# IMX291.net
KiCad netlist of a schematic drawn in Altium Designer
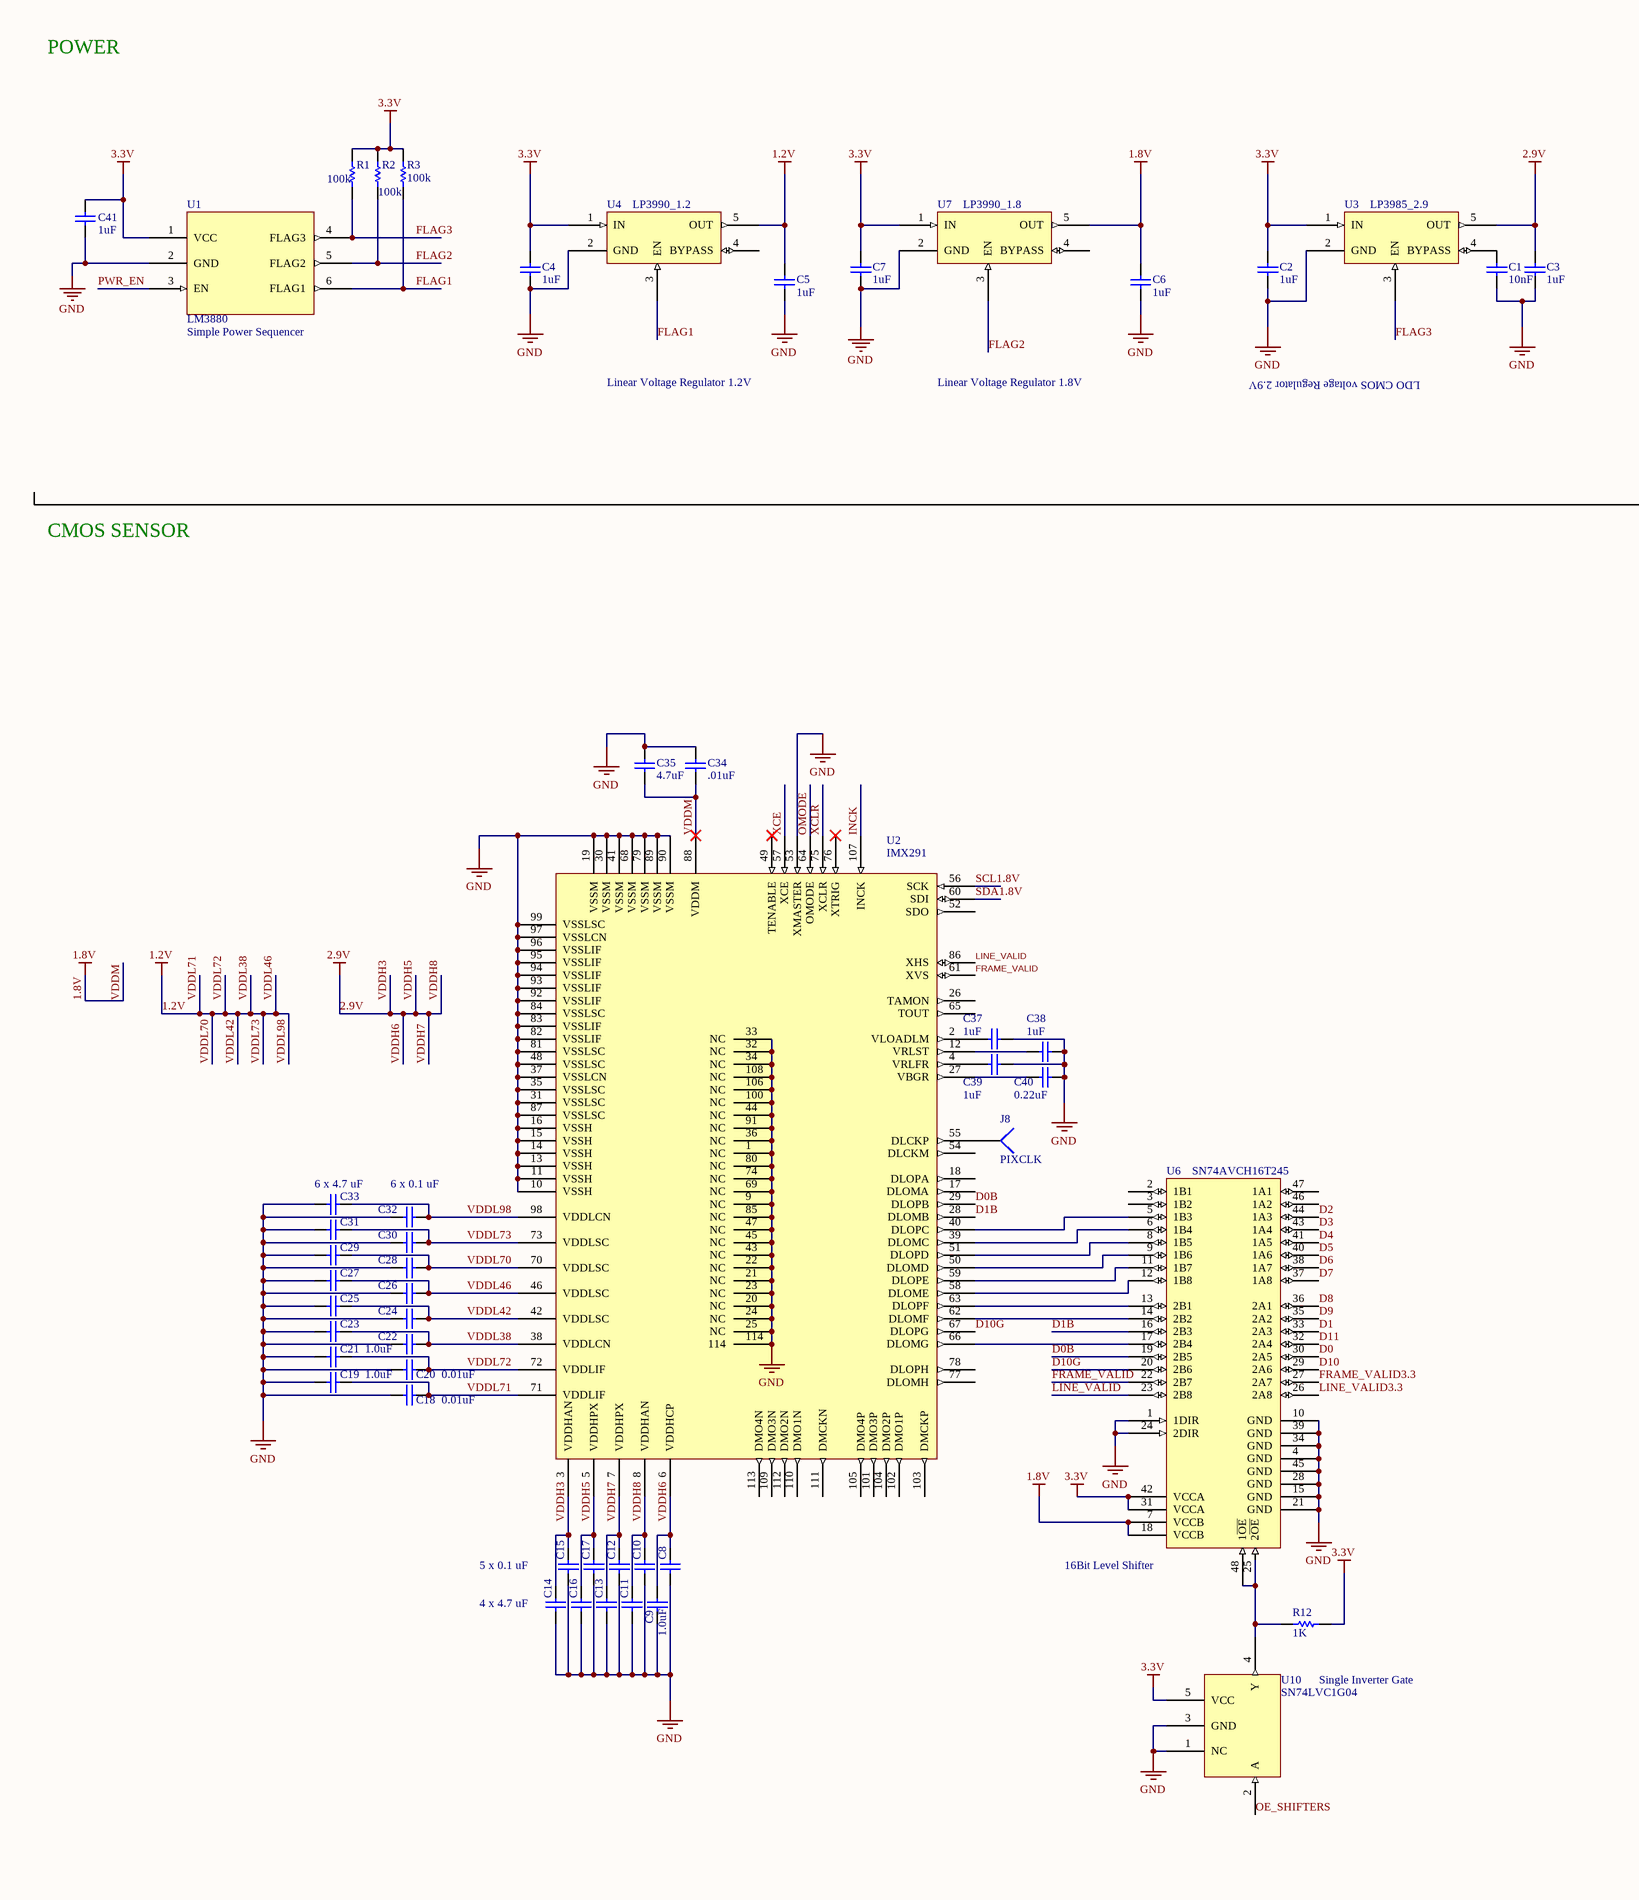
[diagram p0: IMX291.SchDoc, left]
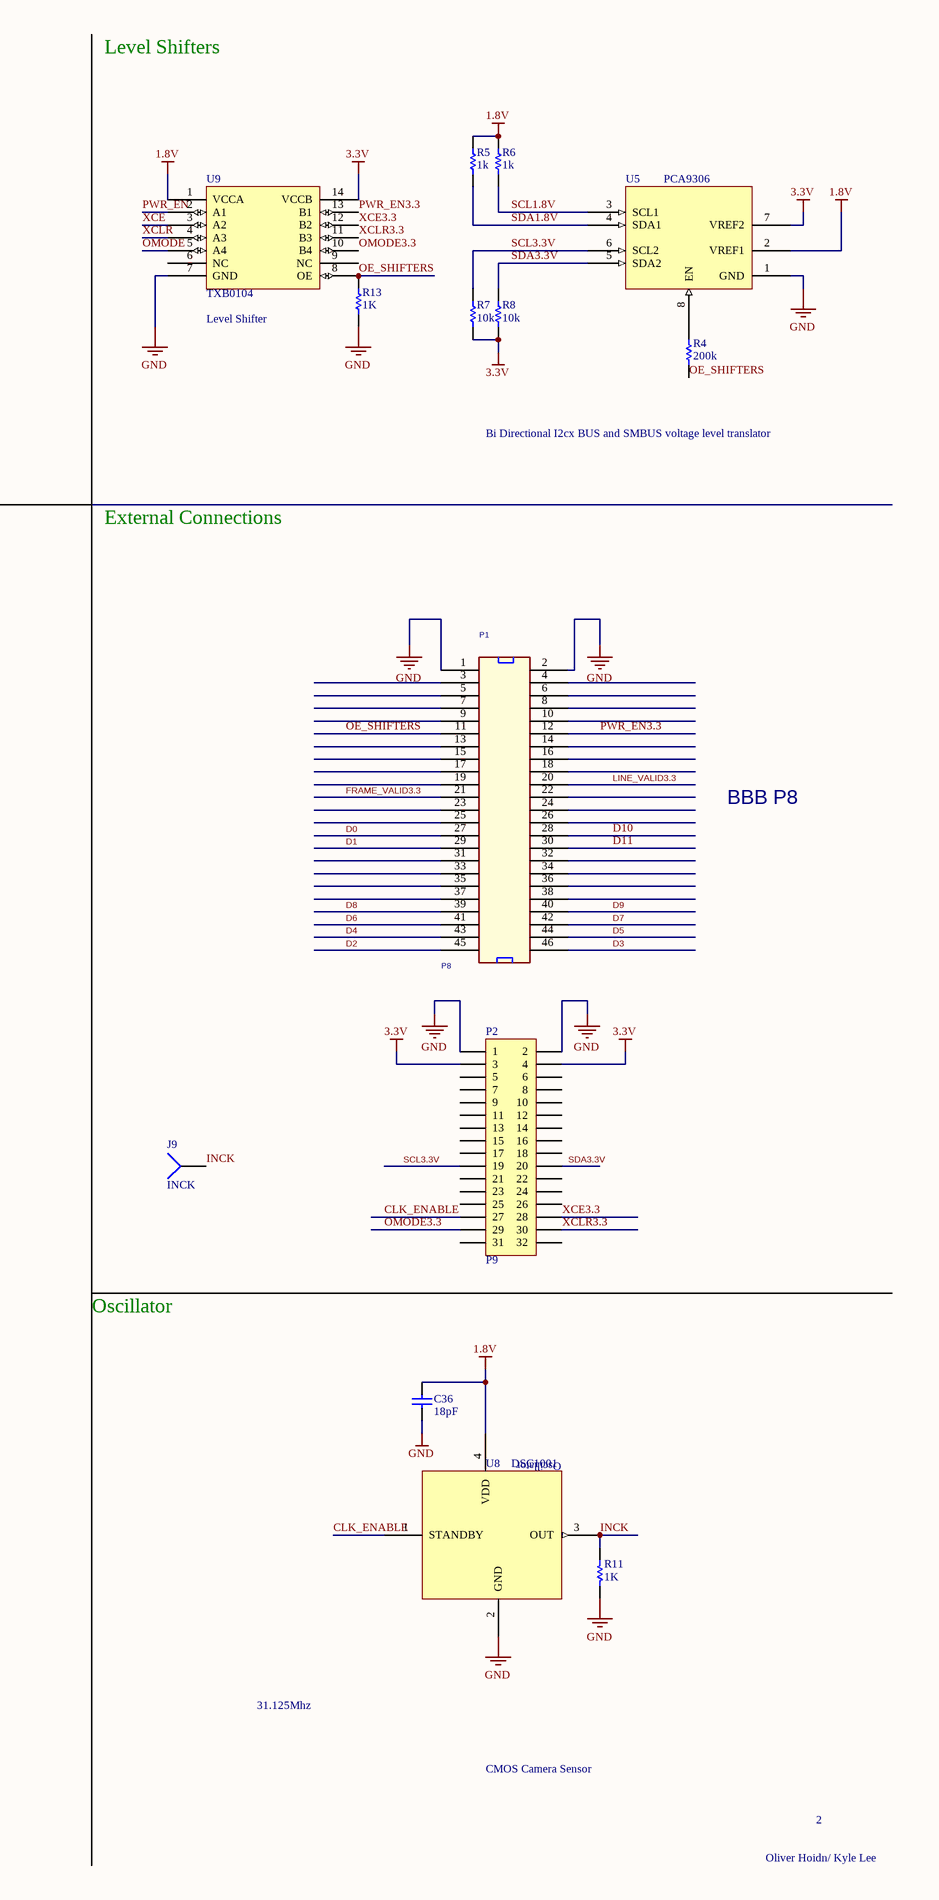
[diagram p1: IMX291.SchDoc, right]

(export (version "E")
  (design (tool "Eeschema 10.0.6"))
  (components
    (comp (ref "C1") (value "10nF") (footprint "0402") (libsource (lib "IMX291") (part "cap")))
    (comp (ref "C2") (value "1uF") (footprint "0402") (libsource (lib "IMX291") (part "cap")))
    (comp (ref "C3") (value "1uF") (footprint "0402") (libsource (lib "IMX291") (part "cap")))
    (comp (ref "C4") (value "1uF") (footprint "0402") (libsource (lib "IMX291") (part "cap")))
    (comp (ref "C5") (value "1uF") (footprint "0402") (libsource (lib "IMX291") (part "cap")))
    (comp (ref "C6") (value "1uF") (footprint "0402") (libsource (lib "IMX291") (part "cap")))
    (comp (ref "C7") (value "1uF") (footprint "0402") (libsource (lib "IMX291") (part "cap")))
    (comp (ref "C8") (value "0.1uF") (footprint "0402") (libsource (lib "IMX291") (part "cap")))
    (comp (ref "C9") (value "1.0uF") (footprint "0402") (libsource (lib "IMX291") (part "cap")))
    (comp (ref "C10") (value "0.1uF") (footprint "0402") (libsource (lib "IMX291") (part "cap")))
    (comp (ref "C11") (value "4.7uF") (footprint "0402") (libsource (lib "IMX291") (part "cap")))
    (comp (ref "C12") (value "0.1uF") (footprint "0402") (libsource (lib "IMX291") (part "cap")))
    (comp (ref "C13") (value "4.7uF") (footprint "0402") (libsource (lib "IMX291") (part "cap")))
    (comp (ref "C14") (value "4.7uF") (footprint "0402") (libsource (lib "IMX291") (part "cap")))
    (comp (ref "C15") (value "0.1uF") (footprint "0402") (libsource (lib "IMX291") (part "cap")))
    (comp (ref "C16") (value "4.7uF") (footprint "0402") (libsource (lib "IMX291") (part "cap")))
    (comp (ref "C17") (value "0.1uF") (footprint "0402") (libsource (lib "IMX291") (part "cap")))
    (comp (ref "C18") (value "0.01uF") (footprint "0402") (libsource (lib "IMX291") (part "cap")))
    (comp (ref "C19") (value "1.0uF") (footprint "0402") (libsource (lib "IMX291") (part "cap")))
    (comp (ref "C20") (value "0.01uF") (footprint "0402") (libsource (lib "IMX291") (part "cap")))
    (comp (ref "C21") (value "1.0uF") (footprint "0402") (libsource (lib "IMX291") (part "cap")))
    (comp (ref "C22") (value "0.1uF") (footprint "0402") (libsource (lib "IMX291") (part "cap")))
    (comp (ref "C23") (value "4.7uF") (footprint "0402") (libsource (lib "IMX291") (part "cap")))
    (comp (ref "C24") (value "0.1uF") (footprint "0402") (libsource (lib "IMX291") (part "cap")))
    (comp (ref "C25") (value "4.7uF") (footprint "0402") (libsource (lib "IMX291") (part "cap")))
    (comp (ref "C26") (value "0.1uF") (footprint "0402") (libsource (lib "IMX291") (part "cap")))
    (comp (ref "C27") (value "4.7uF") (footprint "0402") (libsource (lib "IMX291") (part "cap")))
    (comp (ref "C28") (value "0.1uF") (footprint "0402") (libsource (lib "IMX291") (part "cap")))
    (comp (ref "C29") (value "4.7uF") (footprint "0402") (libsource (lib "IMX291") (part "cap")))
    (comp (ref "C30") (value "0.1uF") (footprint "0402") (libsource (lib "IMX291") (part "cap")))
    (comp (ref "C31") (value "4.7uF") (footprint "0402") (libsource (lib "IMX291") (part "cap")))
    (comp (ref "C32") (value "0.1uF") (footprint "0402") (libsource (lib "IMX291") (part "cap")))
    (comp (ref "C33") (value "4.7uF") (footprint "0402") (libsource (lib "IMX291") (part "cap")))
    (comp (ref "C34") (value ".01uF") (footprint "0402") (libsource (lib "IMX291") (part "cap")))
    (comp (ref "C35") (value "4.7uF") (footprint "0402") (libsource (lib "IMX291") (part "cap")))
    (comp (ref "C36") (value "18pF") (footprint "0402") (libsource (lib "IMX291") (part "cap")))
    (comp (ref "C37") (value "1uF") (footprint "0402") (libsource (lib "IMX291") (part "cap")))
    (comp (ref "C38") (value "1uF") (footprint "0402") (libsource (lib "IMX291") (part "cap")))
    (comp (ref "C39") (value "1uF") (footprint "0402") (libsource (lib "IMX291") (part "cap")))
    (comp (ref "C40") (value "0.22uF") (footprint "0402") (libsource (lib "IMX291") (part "cap")))
    (comp (ref "C41") (value "1uF") (footprint "0402") (libsource (lib "IMX291") (part "cap")))
    (comp (ref "J8")
      (value "PIXCLK")
      (footprint "PIN1")
      (description "Socket")
      (fields (field (name "PUBLISHER") "Altium Limited"))
      (libsource (lib "IMX291") (part "Socket"))
    )
    (comp (ref "J9")
      (value "INCK")
      (footprint "PIN1")
      (description "Socket")
      (fields (field (name "PUBLISHER") "Altium Limited"))
      (libsource (lib "IMX291") (part "Socket"))
    )
    (comp (ref "P1")
      (value "P8")
      (description "CONN HEADER FMAL 46PS.1\" DL GOLD")
      (fields
        (field (name "MANUFACTURER") "Sullins Connector Solutions")
        (field (name "MANUFACTURER PART NUMBER") "PPPC232LFBN-RC")
      )
      (libsource (lib "IMX291") (part "HDR_46_F_2_0.1_0.1"))
    )
    (comp (ref "P2")
      (value "P9")
      (footprint "HDR2X16")
      (fields (field (name "PUBLISHER") "Altium Limited"))
      (libsource (lib "IMX291") (part "Header 16X2"))
    )
    (comp (ref "R1")
      (value "100k")
      (footprint "0402")
      (description "resistor")
      (libsource (lib "IMX291") (part "res"))
    )
    (comp (ref "R2")
      (value "100k")
      (footprint "0402")
      (description "resistor")
      (libsource (lib "IMX291") (part "res"))
    )
    (comp (ref "R3")
      (value "100k")
      (footprint "0402")
      (description "resistor")
      (libsource (lib "IMX291") (part "res"))
    )
    (comp (ref "R4")
      (value "200k")
      (footprint "0402")
      (description "resistor")
      (libsource (lib "IMX291") (part "res"))
    )
    (comp (ref "R5")
      (value "1k")
      (footprint "0402")
      (description "resistor")
      (libsource (lib "IMX291") (part "res"))
    )
    (comp (ref "R6")
      (value "1k")
      (footprint "0402")
      (description "resistor")
      (libsource (lib "IMX291") (part "res"))
    )
    (comp (ref "R7")
      (value "10k")
      (footprint "0603")
      (description "resistor")
      (libsource (lib "IMX291") (part "res"))
    )
    (comp (ref "R8")
      (value "10k")
      (footprint "0603")
      (description "resistor")
      (libsource (lib "IMX291") (part "res"))
    )
    (comp (ref "R11") (value "1K") (footprint "0402") (libsource (lib "") (part "res_1")))
    (comp (ref "R12") (value "1K") (footprint "0402") (libsource (lib "") (part "res_1")))
    (comp (ref "R13") (value "1K") (footprint "0402") (libsource (lib "") (part "res_1")))
    (comp (ref "U1") (value "LM3880") (footprint "SOT23-6_M") (libsource (lib "IMX291") (part "LM3880")))
    (comp (ref "U2")
      (value "IMX291")
      (footprint "LGA110C80P14X11_1200X930X350 -Back View")
      (libsource (lib "IMX291") (part "IMX291"))
    )
    (comp (ref "U3") (value "LP3985_2.9") (footprint "DBV005") (libsource (lib "IMX291") (part "LP3985")))
    (comp (ref "U4") (value "LP3990_1.2") (footprint "DBV005") (libsource (lib "IMX291") (part "LP3990")))
    (comp (ref "U5") (value "PCA9306") (footprint "D008_M") (libsource (lib "IMX291") (part "PCA9306")))
    (comp (ref "U6")
      (value "SN74AVCH16T245")
      (footprint "TSSOP48")
      (libsource (lib "IMX291") (part "SN74AVCH16T245"))
    )
    (comp (ref "U7") (value "LP3990_1.8") (footprint "DBV005") (libsource (lib "IMX291") (part "LP3990")))
    (comp (ref "U8") (value "DSC1001") (footprint "DSC1001") (libsource (lib "IMX291") (part "DSC1001")))
    (comp (ref "U9") (value "TXB0104") (footprint "TSSOP14_M") (libsource (lib "IMX291") (part "TXB0104")))
    (comp (ref "U10")
      (value "SN74LVC1G04")
      (footprint "DBV005")
      (libsource (lib "IMX291") (part "SN74LVC1G04"))
    )
  )
  (nets
    (net (code "1") (name "/CLK_ENABLE") (class "Default")
      (node (ref "P2") (pin "27") (pinfunction "27_27") (pintype "passive"))
      (node (ref "U8") (pin "1") (pinfunction "STANDBY_1") (pintype "passive"))
    )
    (net (code "2") (name "/D0") (class "Default")
      (node (ref "P1") (pin "27") (pinfunction "14_27") (pintype "passive"))
      (node (ref "U6") (pin "30") (pinfunction "2A5_30") (pintype "bidirectional"))
    )
    (net (code "3") (name "/D0B") (class "Default")
      (node (ref "U2") (pin "29") (pinfunction "DLOPB_29") (pintype "output"))
      (node (ref "U6") (pin "19") (pinfunction "2B5_19") (pintype "bidirectional"))
    )
    (net (code "4") (name "/D1") (class "Default")
      (node (ref "P1") (pin "29") (pinfunction "15_29") (pintype "passive"))
      (node (ref "U6") (pin "33") (pinfunction "2A3_33") (pintype "bidirectional"))
    )
    (net (code "5") (name "/D1B") (class "Default")
      (node (ref "U2") (pin "28") (pinfunction "DLOMB_28") (pintype "output"))
      (node (ref "U6") (pin "16") (pinfunction "2B3_16") (pintype "bidirectional"))
    )
    (net (code "6") (name "/D2") (class "Default")
      (node (ref "P1") (pin "45") (pinfunction "23_45") (pintype "passive"))
      (node (ref "U6") (pin "44") (pinfunction "1A3_44") (pintype "bidirectional"))
    )
    (net (code "7") (name "/D3") (class "Default")
      (node (ref "P1") (pin "46") (pinfunction "48_46") (pintype "passive"))
      (node (ref "U6") (pin "43") (pinfunction "1A4_43") (pintype "bidirectional"))
    )
    (net (code "8") (name "/D4") (class "Default")
      (node (ref "P1") (pin "43") (pinfunction "22_43") (pintype "passive"))
      (node (ref "U6") (pin "41") (pinfunction "1A5_41") (pintype "bidirectional"))
    )
    (net (code "9") (name "/D5") (class "Default")
      (node (ref "P1") (pin "44") (pinfunction "47_44") (pintype "passive"))
      (node (ref "U6") (pin "40") (pinfunction "1A6_40") (pintype "bidirectional"))
    )
    (net (code "10") (name "/D6") (class "Default")
      (node (ref "P1") (pin "41") (pinfunction "21_41") (pintype "passive"))
      (node (ref "U6") (pin "38") (pinfunction "1A7_38") (pintype "bidirectional"))
    )
    (net (code "11") (name "/D7") (class "Default")
      (node (ref "P1") (pin "42") (pinfunction "46_42") (pintype "passive"))
      (node (ref "U6") (pin "37") (pinfunction "1A8_37") (pintype "bidirectional"))
    )
    (net (code "12") (name "/D8") (class "Default")
      (node (ref "P1") (pin "39") (pinfunction "20_39") (pintype "passive"))
      (node (ref "U6") (pin "36") (pinfunction "2A1_36") (pintype "bidirectional"))
    )
    (net (code "13") (name "/D9") (class "Default")
      (node (ref "P1") (pin "40") (pinfunction "45_40") (pintype "passive"))
      (node (ref "U6") (pin "35") (pinfunction "2A2_35") (pintype "bidirectional"))
    )
    (net (code "14") (name "/D10") (class "Default")
      (node (ref "P1") (pin "28") (pinfunction "39_28") (pintype "passive"))
      (node (ref "U6") (pin "29") (pinfunction "2A6_29") (pintype "bidirectional"))
    )
    (net (code "15") (name "/D10G") (class "Default")
      (node (ref "U2") (pin "67") (pinfunction "DLOPG_67") (pintype "output"))
      (node (ref "U6") (pin "20") (pinfunction "2B6_20") (pintype "bidirectional"))
    )
    (net (code "16") (name "/D11") (class "Default")
      (node (ref "P1") (pin "30") (pinfunction "40_30") (pintype "passive"))
      (node (ref "U6") (pin "32") (pinfunction "2A4_32") (pintype "bidirectional"))
    )
    (net (code "17") (name "/FLAG1") (class "Default")
      (node (ref "R3") (pin "1") (pinfunction "1_1") (pintype "passive"))
      (node (ref "U1") (pin "6") (pinfunction "FLAG1_6") (pintype "output"))
      (node (ref "U4") (pin "3") (pinfunction "EN_3") (pintype "input"))
    )
    (net (code "18") (name "/FLAG2") (class "Default")
      (node (ref "R2") (pin "1") (pinfunction "1_1") (pintype "passive"))
      (node (ref "U1") (pin "5") (pinfunction "FLAG2_5") (pintype "output"))
      (node (ref "U7") (pin "3") (pinfunction "EN_3") (pintype "input"))
    )
    (net (code "19") (name "/FLAG3") (class "Default")
      (node (ref "R1") (pin "1") (pinfunction "1_1") (pintype "passive"))
      (node (ref "U1") (pin "4") (pinfunction "FLAG3_4") (pintype "output"))
      (node (ref "U3") (pin "3") (pinfunction "EN_3") (pintype "input"))
    )
    (net (code "20") (name "/FRAME_VALID") (class "Default")
      (node (ref "U2") (pin "61") (pinfunction "XVS_61") (pintype "bidirectional"))
      (node (ref "U6") (pin "22") (pinfunction "2B7_22") (pintype "bidirectional"))
    )
    (net (code "21") (name "/FRAME_VALID3.3") (class "Default")
      (node (ref "P1") (pin "21") (pinfunction "11_21") (pintype "passive"))
      (node (ref "U6") (pin "27") (pinfunction "2A7_27") (pintype "bidirectional"))
    )
    (net (code "22") (name "/INCK") (class "Default")
      (node (ref "J9") (pin "1") (pinfunction "1_1") (pintype "passive"))
      (node (ref "R11") (pin "2") (pinfunction "2_2") (pintype "passive"))
      (node (ref "U2") (pin "107") (pinfunction "INCK_107") (pintype "input"))
      (node (ref "U8") (pin "3") (pinfunction "OUT_3") (pintype "output"))
    )
    (net (code "23") (name "/LINE_VALID") (class "Default")
      (node (ref "U2") (pin "86") (pinfunction "XHS_86") (pintype "bidirectional"))
      (node (ref "U6") (pin "23") (pinfunction "2B8_23") (pintype "bidirectional"))
    )
    (net (code "24") (name "/LINE_VALID3.3") (class "Default")
      (node (ref "P1") (pin "20") (pinfunction "35_20") (pintype "passive"))
      (node (ref "U6") (pin "26") (pinfunction "2A8_26") (pintype "bidirectional"))
    )
    (net (code "25") (name "/OE_SHIFTERS") (class "Default")
      (node (ref "P1") (pin "11") (pinfunction "6_11") (pintype "passive"))
      (node (ref "R13") (pin "2") (pinfunction "2_2") (pintype "passive"))
      (node (ref "R4") (pin "1") (pinfunction "1_1") (pintype "passive"))
      (node (ref "U10") (pin "2") (pinfunction "A_2") (pintype "input"))
      (node (ref "U9") (pin "8") (pinfunction "OE_8") (pintype "bidirectional"))
    )
    (net (code "26") (name "/OMODE") (class "Default")
      (node (ref "U2") (pin "64") (pinfunction "OMODE_64") (pintype "input"))
      (node (ref "U9") (pin "5") (pinfunction "A4_5") (pintype "bidirectional"))
    )
    (net (code "27") (name "/OMODE3.3") (class "Default")
      (node (ref "P2") (pin "29") (pinfunction "29_29") (pintype "passive"))
      (node (ref "U9") (pin "10") (pinfunction "B4_10") (pintype "bidirectional"))
    )
    (net (code "28") (name "/PWR_EN") (class "Default")
      (node (ref "U1") (pin "3") (pinfunction "EN_3") (pintype "input"))
      (node (ref "U9") (pin "2") (pinfunction "A1_2") (pintype "bidirectional"))
    )
    (net (code "29") (name "/PWR_EN3.3") (class "Default")
      (node (ref "P1") (pin "12") (pinfunction "31_12") (pintype "passive"))
      (node (ref "U9") (pin "13") (pinfunction "B1_13") (pintype "bidirectional"))
    )
    (net (code "30") (name "/SCL1.8V") (class "Default")
      (node (ref "R6") (pin "1") (pinfunction "1_1") (pintype "passive"))
      (node (ref "U2") (pin "56") (pinfunction "SCK_56") (pintype "input"))
      (node (ref "U5") (pin "3") (pinfunction "SCL1_3") (pintype "input"))
    )
    (net (code "31") (name "/SCL3.3V") (class "Default")
      (node (ref "P2") (pin "19") (pinfunction "19_19") (pintype "passive"))
      (node (ref "R7") (pin "2") (pinfunction "2_2") (pintype "passive"))
      (node (ref "U5") (pin "6") (pinfunction "SCL2_6") (pintype "input"))
    )
    (net (code "32") (name "/SDA1.8V") (class "Default")
      (node (ref "R5") (pin "1") (pinfunction "1_1") (pintype "passive"))
      (node (ref "U2") (pin "60") (pinfunction "SDI_60") (pintype "bidirectional"))
      (node (ref "U5") (pin "4") (pinfunction "SDA1_4") (pintype "input"))
    )
    (net (code "33") (name "/SDA3.3V") (class "Default")
      (node (ref "P2") (pin "20") (pinfunction "20_20") (pintype "passive"))
      (node (ref "R8") (pin "2") (pinfunction "2_2") (pintype "passive"))
      (node (ref "U5") (pin "5") (pinfunction "SDA2_5") (pintype "input"))
    )
    (net (code "34") (name "/XCE") (class "Default")
      (node (ref "U2") (pin "57") (pinfunction "XCE_57") (pintype "input"))
      (node (ref "U9") (pin "3") (pinfunction "A2_3") (pintype "bidirectional"))
    )
    (net (code "35") (name "/XCE3.3") (class "Default")
      (node (ref "P2") (pin "28") (pinfunction "28_28") (pintype "passive"))
      (node (ref "U9") (pin "12") (pinfunction "B2_12") (pintype "bidirectional"))
    )
    (net (code "36") (name "/XCLR") (class "Default")
      (node (ref "U2") (pin "75") (pinfunction "XCLR_75") (pintype "input"))
      (node (ref "U9") (pin "4") (pinfunction "A3_4") (pintype "bidirectional"))
    )
    (net (code "37") (name "/XCLR3.3") (class "Default")
      (node (ref "P2") (pin "30") (pinfunction "30_30") (pintype "passive"))
      (node (ref "U9") (pin "11") (pinfunction "B3_11") (pintype "bidirectional"))
    )
    (net (code "38") (name "1.2V") (class "Default")
      (node (ref "C18") (pin "2") (pinfunction "2_2") (pintype "passive"))
      (node (ref "C19") (pin "2") (pinfunction "2_2") (pintype "passive"))
      (node (ref "C20") (pin "2") (pinfunction "2_2") (pintype "passive"))
      (node (ref "C21") (pin "2") (pinfunction "2_2") (pintype "passive"))
      (node (ref "C22") (pin "2") (pinfunction "2_2") (pintype "passive"))
      (node (ref "C23") (pin "2") (pinfunction "2_2") (pintype "passive"))
      (node (ref "C24") (pin "2") (pinfunction "2_2") (pintype "passive"))
      (node (ref "C25") (pin "2") (pinfunction "2_2") (pintype "passive"))
      (node (ref "C26") (pin "2") (pinfunction "2_2") (pintype "passive"))
      (node (ref "C27") (pin "2") (pinfunction "2_2") (pintype "passive"))
      (node (ref "C28") (pin "2") (pinfunction "2_2") (pintype "passive"))
      (node (ref "C29") (pin "2") (pinfunction "2_2") (pintype "passive"))
      (node (ref "C30") (pin "2") (pinfunction "2_2") (pintype "passive"))
      (node (ref "C31") (pin "2") (pinfunction "2_2") (pintype "passive"))
      (node (ref "C32") (pin "2") (pinfunction "2_2") (pintype "passive"))
      (node (ref "C33") (pin "2") (pinfunction "2_2") (pintype "passive"))
      (node (ref "C5") (pin "2") (pinfunction "2_2") (pintype "passive"))
      (node (ref "U2") (pin "38") (pinfunction "VDDLCN_38") (pintype "power_in"))
      (node (ref "U2") (pin "42") (pinfunction "VDDLSC_42") (pintype "power_in"))
      (node (ref "U2") (pin "46") (pinfunction "VDDLSC_46") (pintype "power_in"))
      (node (ref "U2") (pin "70") (pinfunction "VDDLSC_70") (pintype "power_in"))
      (node (ref "U2") (pin "71") (pinfunction "VDDLIF_71") (pintype "power_in"))
      (node (ref "U2") (pin "72") (pinfunction "VDDLIF_72") (pintype "power_in"))
      (node (ref "U2") (pin "73") (pinfunction "VDDLSC_73") (pintype "power_in"))
      (node (ref "U2") (pin "98") (pinfunction "VDDLCN_98") (pintype "power_in"))
      (node (ref "U4") (pin "5") (pinfunction "OUT_5") (pintype "output"))
    )
    (net (code "39") (name "1.8V") (class "Default")
      (node (ref "C34") (pin "1") (pinfunction "1_1") (pintype "passive"))
      (node (ref "C35") (pin "1") (pinfunction "1_1") (pintype "passive"))
      (node (ref "C36") (pin "2") (pinfunction "2_2") (pintype "passive"))
      (node (ref "C6") (pin "2") (pinfunction "2_2") (pintype "passive"))
      (node (ref "R5") (pin "2") (pinfunction "2_2") (pintype "passive"))
      (node (ref "R6") (pin "2") (pinfunction "2_2") (pintype "passive"))
      (node (ref "U2") (pin "88") (pinfunction "VDDM_88") (pintype "power_in"))
      (node (ref "U5") (pin "2") (pinfunction "VREF1_2") (pintype "power_in"))
      (node (ref "U6") (pin "18") (pinfunction "VCCB_18") (pintype "power_in"))
      (node (ref "U6") (pin "7") (pinfunction "VCCB_7") (pintype "power_in"))
      (node (ref "U7") (pin "5") (pinfunction "OUT_5") (pintype "output"))
      (node (ref "U8") (pin "4") (pinfunction "VDD_4") (pintype "passive"))
      (node (ref "U9") (pin "1") (pinfunction "VCCA_1") (pintype "power_in"))
    )
    (net (code "40") (name "2.9V") (class "Default")
      (node (ref "C10") (pin "2") (pinfunction "2_2") (pintype "passive"))
      (node (ref "C11") (pin "2") (pinfunction "2_2") (pintype "passive"))
      (node (ref "C12") (pin "2") (pinfunction "2_2") (pintype "passive"))
      (node (ref "C13") (pin "2") (pinfunction "2_2") (pintype "passive"))
      (node (ref "C14") (pin "2") (pinfunction "2_2") (pintype "passive"))
      (node (ref "C15") (pin "2") (pinfunction "2_2") (pintype "passive"))
      (node (ref "C16") (pin "2") (pinfunction "2_2") (pintype "passive"))
      (node (ref "C17") (pin "2") (pinfunction "2_2") (pintype "passive"))
      (node (ref "C3") (pin "2") (pinfunction "2_2") (pintype "passive"))
      (node (ref "C8") (pin "1") (pinfunction "1_1") (pintype "passive"))
      (node (ref "C9") (pin "1") (pinfunction "1_1") (pintype "passive"))
      (node (ref "U2") (pin "3") (pinfunction "VDDHAN_3") (pintype "power_in"))
      (node (ref "U2") (pin "5") (pinfunction "VDDHPX_5") (pintype "power_in"))
      (node (ref "U2") (pin "6") (pinfunction "VDDHCP_6") (pintype "power_in"))
      (node (ref "U2") (pin "7") (pinfunction "VDDHPX_7") (pintype "power_in"))
      (node (ref "U2") (pin "8") (pinfunction "VDDHAN_8") (pintype "power_in"))
      (node (ref "U3") (pin "5") (pinfunction "OUT_5") (pintype "output"))
    )
    (net (code "41") (name "3.3V") (class "Default")
      (node (ref "C2") (pin "1") (pinfunction "1_1") (pintype "passive"))
      (node (ref "C4") (pin "1") (pinfunction "1_1") (pintype "passive"))
      (node (ref "C41") (pin "2") (pinfunction "2_2") (pintype "passive"))
      (node (ref "C7") (pin "1") (pinfunction "1_1") (pintype "passive"))
      (node (ref "P2") (pin "3") (pinfunction "3_3") (pintype "passive"))
      (node (ref "P2") (pin "4") (pinfunction "4_4") (pintype "passive"))
      (node (ref "R1") (pin "2") (pinfunction "2_2") (pintype "passive"))
      (node (ref "R12") (pin "2") (pinfunction "2_2") (pintype "passive"))
      (node (ref "R2") (pin "2") (pinfunction "2_2") (pintype "passive"))
      (node (ref "R3") (pin "2") (pinfunction "2_2") (pintype "passive"))
      (node (ref "R7") (pin "1") (pinfunction "1_1") (pintype "passive"))
      (node (ref "R8") (pin "1") (pinfunction "1_1") (pintype "passive"))
      (node (ref "U1") (pin "1") (pinfunction "VCC_1") (pintype "power_in"))
      (node (ref "U10") (pin "5") (pinfunction "VCC_5") (pintype "power_in"))
      (node (ref "U3") (pin "1") (pinfunction "IN_1") (pintype "input"))
      (node (ref "U4") (pin "1") (pinfunction "IN_1") (pintype "input"))
      (node (ref "U5") (pin "7") (pinfunction "VREF2_7") (pintype "power_in"))
      (node (ref "U6") (pin "31") (pinfunction "VCCA_31") (pintype "power_in"))
      (node (ref "U6") (pin "42") (pinfunction "VCCA_42") (pintype "power_in"))
      (node (ref "U7") (pin "1") (pinfunction "IN_1") (pintype "input"))
      (node (ref "U9") (pin "14") (pinfunction "VCCB_14") (pintype "power_in"))
    )
    (net (code "42") (name "GND") (class "Default")
      (node (ref "C1") (pin "2") (pinfunction "2_2") (pintype "passive"))
      (node (ref "C10") (pin "1") (pinfunction "1_1") (pintype "passive"))
      (node (ref "C11") (pin "1") (pinfunction "1_1") (pintype "passive"))
      (node (ref "C12") (pin "1") (pinfunction "1_1") (pintype "passive"))
      (node (ref "C13") (pin "1") (pinfunction "1_1") (pintype "passive"))
      (node (ref "C14") (pin "1") (pinfunction "1_1") (pintype "passive"))
      (node (ref "C15") (pin "1") (pinfunction "1_1") (pintype "passive"))
      (node (ref "C16") (pin "1") (pinfunction "1_1") (pintype "passive"))
      (node (ref "C17") (pin "1") (pinfunction "1_1") (pintype "passive"))
      (node (ref "C18") (pin "1") (pinfunction "1_1") (pintype "passive"))
      (node (ref "C19") (pin "1") (pinfunction "1_1") (pintype "passive"))
      (node (ref "C2") (pin "2") (pinfunction "2_2") (pintype "passive"))
      (node (ref "C20") (pin "1") (pinfunction "1_1") (pintype "passive"))
      (node (ref "C21") (pin "1") (pinfunction "1_1") (pintype "passive"))
      (node (ref "C22") (pin "1") (pinfunction "1_1") (pintype "passive"))
      (node (ref "C23") (pin "1") (pinfunction "1_1") (pintype "passive"))
      (node (ref "C24") (pin "1") (pinfunction "1_1") (pintype "passive"))
      (node (ref "C25") (pin "1") (pinfunction "1_1") (pintype "passive"))
      (node (ref "C26") (pin "1") (pinfunction "1_1") (pintype "passive"))
      (node (ref "C27") (pin "1") (pinfunction "1_1") (pintype "passive"))
      (node (ref "C28") (pin "1") (pinfunction "1_1") (pintype "passive"))
      (node (ref "C29") (pin "1") (pinfunction "1_1") (pintype "passive"))
      (node (ref "C3") (pin "1") (pinfunction "1_1") (pintype "passive"))
      (node (ref "C30") (pin "1") (pinfunction "1_1") (pintype "passive"))
      (node (ref "C31") (pin "1") (pinfunction "1_1") (pintype "passive"))
      (node (ref "C32") (pin "1") (pinfunction "1_1") (pintype "passive"))
      (node (ref "C33") (pin "1") (pinfunction "1_1") (pintype "passive"))
      (node (ref "C34") (pin "2") (pinfunction "2_2") (pintype "passive"))
      (node (ref "C35") (pin "2") (pinfunction "2_2") (pintype "passive"))
      (node (ref "C36") (pin "1") (pinfunction "1_1") (pintype "passive"))
      (node (ref "C37") (pin "2") (pinfunction "2_2") (pintype "passive"))
      (node (ref "C38") (pin "2") (pinfunction "2_2") (pintype "passive"))
      (node (ref "C39") (pin "2") (pinfunction "2_2") (pintype "passive"))
      (node (ref "C4") (pin "2") (pinfunction "2_2") (pintype "passive"))
      (node (ref "C40") (pin "2") (pinfunction "2_2") (pintype "passive"))
      (node (ref "C41") (pin "1") (pinfunction "1_1") (pintype "passive"))
      (node (ref "C5") (pin "1") (pinfunction "1_1") (pintype "passive"))
      (node (ref "C6") (pin "1") (pinfunction "1_1") (pintype "passive"))
      (node (ref "C7") (pin "2") (pinfunction "2_2") (pintype "passive"))
      (node (ref "C8") (pin "2") (pinfunction "2_2") (pintype "passive"))
      (node (ref "C9") (pin "2") (pinfunction "2_2") (pintype "passive"))
      (node (ref "P1") (pin "1") (pinfunction "1_1") (pintype "passive"))
      (node (ref "P1") (pin "2") (pinfunction "26_2") (pintype "passive"))
      (node (ref "P2") (pin "1") (pinfunction "1_1") (pintype "passive"))
      (node (ref "P2") (pin "2") (pinfunction "2_2") (pintype "passive"))
      (node (ref "R11") (pin "1") (pinfunction "1_1") (pintype "passive"))
      (node (ref "R13") (pin "1") (pinfunction "1_1") (pintype "passive"))
      (node (ref "U1") (pin "2") (pinfunction "GND_2") (pintype "power_in"))
      (node (ref "U10") (pin "1") (pinfunction "NC_1") (pintype "passive"))
      (node (ref "U10") (pin "3") (pinfunction "GND_3") (pintype "power_in"))
      (node (ref "U2") (pin "1") (pinfunction "NC_1") (pintype "passive"))
      (node (ref "U2") (pin "10") (pinfunction "VSSH_10") (pintype "power_in"))
      (node (ref "U2") (pin "100") (pinfunction "NC_100") (pintype "passive"))
      (node (ref "U2") (pin "106") (pinfunction "NC_106") (pintype "passive"))
      (node (ref "U2") (pin "108") (pinfunction "NC_108") (pintype "passive"))
      (node (ref "U2") (pin "11") (pinfunction "VSSH_11") (pintype "power_in"))
      (node (ref "U2") (pin "114") (pinfunction "114_114") (pintype "passive"))
      (node (ref "U2") (pin "13") (pinfunction "VSSH_13") (pintype "power_in"))
      (node (ref "U2") (pin "14") (pinfunction "VSSH_14") (pintype "power_in"))
      (node (ref "U2") (pin "15") (pinfunction "VSSH_15") (pintype "power_in"))
      (node (ref "U2") (pin "16") (pinfunction "VSSH_16") (pintype "power_in"))
      (node (ref "U2") (pin "19") (pinfunction "VSSM_19") (pintype "power_in"))
      (node (ref "U2") (pin "20") (pinfunction "NC_20") (pintype "passive"))
      (node (ref "U2") (pin "21") (pinfunction "NC_21") (pintype "passive"))
      (node (ref "U2") (pin "22") (pinfunction "NC_22") (pintype "passive"))
      (node (ref "U2") (pin "23") (pinfunction "NC_23") (pintype "passive"))
      (node (ref "U2") (pin "24") (pinfunction "NC_24") (pintype "passive"))
      (node (ref "U2") (pin "25") (pinfunction "NC_25") (pintype "passive"))
      (node (ref "U2") (pin "30") (pinfunction "VSSM_30") (pintype "power_in"))
      (node (ref "U2") (pin "31") (pinfunction "VSSLSC_31") (pintype "power_in"))
      (node (ref "U2") (pin "32") (pinfunction "NC_32") (pintype "passive"))
      (node (ref "U2") (pin "33") (pinfunction "NC_33") (pintype "passive"))
      (node (ref "U2") (pin "34") (pinfunction "NC_34") (pintype "passive"))
      (node (ref "U2") (pin "35") (pinfunction "VSSLSC_35") (pintype "power_in"))
      (node (ref "U2") (pin "36") (pinfunction "NC_36") (pintype "passive"))
      (node (ref "U2") (pin "37") (pinfunction "VSSLCN_37") (pintype "power_in"))
      (node (ref "U2") (pin "41") (pinfunction "VSSM_41") (pintype "power_in"))
      (node (ref "U2") (pin "43") (pinfunction "NC_43") (pintype "passive"))
      (node (ref "U2") (pin "44") (pinfunction "NC_44") (pintype "passive"))
      (node (ref "U2") (pin "45") (pinfunction "NC_45") (pintype "passive"))
      (node (ref "U2") (pin "47") (pinfunction "NC_47") (pintype "passive"))
      (node (ref "U2") (pin "48") (pinfunction "VSSLSC_48") (pintype "power_in"))
      (node (ref "U2") (pin "53") (pinfunction "XMASTER_53") (pintype "input"))
      (node (ref "U2") (pin "68") (pinfunction "VSSM_68") (pintype "power_in"))
      (node (ref "U2") (pin "69") (pinfunction "NC_69") (pintype "passive"))
      (node (ref "U2") (pin "74") (pinfunction "NC_74") (pintype "passive"))
      (node (ref "U2") (pin "79") (pinfunction "VSSM_79") (pintype "power_in"))
      (node (ref "U2") (pin "80") (pinfunction "NC_80") (pintype "passive"))
      (node (ref "U2") (pin "81") (pinfunction "VSSLSC_81") (pintype "power_in"))
      (node (ref "U2") (pin "82") (pinfunction "VSSLIF_82") (pintype "power_in"))
      (node (ref "U2") (pin "83") (pinfunction "VSSLIF_83") (pintype "power_in"))
      (node (ref "U2") (pin "84") (pinfunction "VSSLSC_84") (pintype "power_in"))
      (node (ref "U2") (pin "85") (pinfunction "NC_85") (pintype "passive"))
      (node (ref "U2") (pin "87") (pinfunction "VSSLSC_87") (pintype "power_in"))
      (node (ref "U2") (pin "89") (pinfunction "VSSM_89") (pintype "power_in"))
      (node (ref "U2") (pin "9") (pinfunction "NC_9") (pintype "passive"))
      (node (ref "U2") (pin "90") (pinfunction "VSSM_90") (pintype "power_in"))
      (node (ref "U2") (pin "91") (pinfunction "NC_91") (pintype "passive"))
      (node (ref "U2") (pin "92") (pinfunction "VSSLIF_92") (pintype "power_in"))
      (node (ref "U2") (pin "93") (pinfunction "VSSLIF_93") (pintype "power_in"))
      (node (ref "U2") (pin "94") (pinfunction "VSSLIF_94") (pintype "power_in"))
      (node (ref "U2") (pin "95") (pinfunction "VSSLIF_95") (pintype "power_in"))
      (node (ref "U2") (pin "96") (pinfunction "VSSLIF_96") (pintype "power_in"))
      (node (ref "U2") (pin "97") (pinfunction "VSSLCN_97") (pintype "power_in"))
      (node (ref "U2") (pin "99") (pinfunction "VSSLSC_99") (pintype "power_in"))
      (node (ref "U3") (pin "2") (pinfunction "GND_2") (pintype "power_in"))
      (node (ref "U4") (pin "2") (pinfunction "GND_2") (pintype "power_in"))
      (node (ref "U5") (pin "1") (pinfunction "GND_1") (pintype "power_in"))
      (node (ref "U6") (pin "1") (pinfunction "1DIR_1") (pintype "input"))
      (node (ref "U6") (pin "10") (pinfunction "GND_10") (pintype "power_in"))
      (node (ref "U6") (pin "15") (pinfunction "GND_15") (pintype "power_in"))
      (node (ref "U6") (pin "21") (pinfunction "GND_21") (pintype "power_in"))
      (node (ref "U6") (pin "24") (pinfunction "2DIR_24") (pintype "input"))
      (node (ref "U6") (pin "28") (pinfunction "GND_28") (pintype "power_in"))
      (node (ref "U6") (pin "34") (pinfunction "GND_34") (pintype "power_in"))
      (node (ref "U6") (pin "39") (pinfunction "GND_39") (pintype "power_in"))
      (node (ref "U6") (pin "4") (pinfunction "GND_4") (pintype "power_in"))
      (node (ref "U6") (pin "45") (pinfunction "GND_45") (pintype "power_in"))
      (node (ref "U7") (pin "2") (pinfunction "GND_2") (pintype "power_in"))
      (node (ref "U8") (pin "2") (pinfunction "GND_2") (pintype "passive"))
      (node (ref "U9") (pin "7") (pinfunction "GND_7") (pintype "power_in"))
    )
    (net (code "43") (name "Net-(U2-DLCKP)") (class "Default")
      (node (ref "J8") (pin "1") (pinfunction "1_1") (pintype "passive"))
      (node (ref "U2") (pin "55") (pinfunction "DLCKP_55") (pintype "output"))
    )
    (net (code "44") (name "Net-(U2-DLOMC)") (class "Default")
      (node (ref "U2") (pin "39") (pinfunction "DLOMC_39") (pintype "output"))
      (node (ref "U6") (pin "6") (pinfunction "1B4_6") (pintype "bidirectional"))
    )
    (net (code "45") (name "Net-(U2-DLOMD)") (class "Default")
      (node (ref "U2") (pin "50") (pinfunction "DLOMD_50") (pintype "output"))
      (node (ref "U6") (pin "9") (pinfunction "1B6_9") (pintype "bidirectional"))
    )
    (net (code "46") (name "Net-(U2-DLOME)") (class "Default")
      (node (ref "U2") (pin "58") (pinfunction "DLOME_58") (pintype "output"))
      (node (ref "U6") (pin "12") (pinfunction "1B8_12") (pintype "bidirectional"))
    )
    (net (code "47") (name "Net-(U2-DLOMF)") (class "Default")
      (node (ref "U2") (pin "62") (pinfunction "DLOMF_62") (pintype "output"))
      (node (ref "U6") (pin "14") (pinfunction "2B2_14") (pintype "bidirectional"))
    )
    (net (code "48") (name "Net-(U2-DLOMG)") (class "Default")
      (node (ref "U2") (pin "66") (pinfunction "DLOMG_66") (pintype "output"))
      (node (ref "U6") (pin "17") (pinfunction "2B4_17") (pintype "bidirectional"))
    )
    (net (code "49") (name "Net-(U2-DLOPC)") (class "Default")
      (node (ref "U2") (pin "40") (pinfunction "DLOPC_40") (pintype "output"))
      (node (ref "U6") (pin "5") (pinfunction "1B3_5") (pintype "bidirectional"))
    )
    (net (code "50") (name "Net-(U2-DLOPD)") (class "Default")
      (node (ref "U2") (pin "51") (pinfunction "DLOPD_51") (pintype "output"))
      (node (ref "U6") (pin "8") (pinfunction "1B5_8") (pintype "bidirectional"))
    )
    (net (code "51") (name "Net-(U2-DLOPE)") (class "Default")
      (node (ref "U2") (pin "59") (pinfunction "DLOPE_59") (pintype "output"))
      (node (ref "U6") (pin "11") (pinfunction "1B7_11") (pintype "bidirectional"))
    )
    (net (code "52") (name "Net-(U2-DLOPF)") (class "Default")
      (node (ref "U2") (pin "63") (pinfunction "DLOPF_63") (pintype "output"))
      (node (ref "U6") (pin "13") (pinfunction "2B1_13") (pintype "bidirectional"))
    )
    (net (code "53") (name "Net-(U2-VBGR)") (class "Default")
      (node (ref "C40") (pin "1") (pinfunction "1_1") (pintype "passive"))
      (node (ref "U2") (pin "27") (pinfunction "VBGR_27") (pintype "output"))
    )
    (net (code "54") (name "Net-(U2-VLOADLM)") (class "Default")
      (node (ref "C37") (pin "1") (pinfunction "1_1") (pintype "passive"))
      (node (ref "U2") (pin "2") (pinfunction "VLOADLM_2") (pintype "output"))
    )
    (net (code "55") (name "Net-(U2-VRLFR)") (class "Default")
      (node (ref "C39") (pin "1") (pinfunction "1_1") (pintype "passive"))
      (node (ref "U2") (pin "4") (pinfunction "VRLFR_4") (pintype "output"))
    )
    (net (code "56") (name "Net-(U2-VRLST)") (class "Default")
      (node (ref "C38") (pin "1") (pinfunction "1_1") (pintype "passive"))
      (node (ref "U2") (pin "12") (pinfunction "VRLST_12") (pintype "output"))
    )
    (net (code "57") (name "Net-(U3-BYPASS)") (class "Default")
      (node (ref "C1") (pin "1") (pinfunction "1_1") (pintype "passive"))
      (node (ref "U3") (pin "4") (pinfunction "BYPASS_4") (pintype "bidirectional"))
    )
    (net (code "58") (name "Net-(U5-EN)") (class "Default")
      (node (ref "R4") (pin "2") (pinfunction "2_2") (pintype "passive"))
      (node (ref "U5") (pin "8") (pinfunction "EN_8") (pintype "input"))
    )
    (net (code "59") (name "Net-(U10-Y)") (class "Default")
      (node (ref "R12") (pin "1") (pinfunction "1_1") (pintype "passive"))
      (node (ref "U10") (pin "4") (pinfunction "Y_4") (pintype "output"))
      (node (ref "U6") (pin "25") (pinfunction "2~{OE}_25") (pintype "input"))
      (node (ref "U6") (pin "48") (pinfunction "1~{OE}_48") (pintype "input"))
    )
    (net (code "60") (name "unconnected-(P1-2-Pad3)") (class "Default")
      (node (ref "P1") (pin "3") (pinfunction "2_3") (pintype "passive"))
    )
    (net (code "61") (name "unconnected-(P1-3-Pad5)") (class "Default")
      (node (ref "P1") (pin "5") (pinfunction "3_5") (pintype "passive"))
    )
    (net (code "62") (name "unconnected-(P1-4-Pad7)") (class "Default")
      (node (ref "P1") (pin "7") (pinfunction "4_7") (pintype "passive"))
    )
    (net (code "63") (name "unconnected-(P1-5-Pad9)") (class "Default")
      (node (ref "P1") (pin "9") (pinfunction "5_9") (pintype "passive"))
    )
    (net (code "64") (name "unconnected-(P1-7-Pad13)") (class "Default")
      (node (ref "P1") (pin "13") (pinfunction "7_13") (pintype "passive"))
    )
    (net (code "65") (name "unconnected-(P1-8-Pad15)") (class "Default")
      (node (ref "P1") (pin "15") (pinfunction "8_15") (pintype "passive"))
    )
    (net (code "66") (name "unconnected-(P1-9-Pad17)") (class "Default")
      (node (ref "P1") (pin "17") (pinfunction "9_17") (pintype "passive"))
    )
    (net (code "67") (name "unconnected-(P1-10-Pad19)") (class "Default")
      (node (ref "P1") (pin "19") (pinfunction "10_19") (pintype "passive"))
    )
    (net (code "68") (name "unconnected-(P1-12-Pad23)") (class "Default")
      (node (ref "P1") (pin "23") (pinfunction "12_23") (pintype "passive"))
    )
    (net (code "69") (name "unconnected-(P1-13-Pad25)") (class "Default")
      (node (ref "P1") (pin "25") (pinfunction "13_25") (pintype "passive"))
    )
    (net (code "70") (name "unconnected-(P1-16-Pad31)") (class "Default")
      (node (ref "P1") (pin "31") (pinfunction "16_31") (pintype "passive"))
    )
    (net (code "71") (name "unconnected-(P1-17-Pad33)") (class "Default")
      (node (ref "P1") (pin "33") (pinfunction "17_33") (pintype "passive"))
    )
    (net (code "72") (name "unconnected-(P1-18-Pad35)") (class "Default")
      (node (ref "P1") (pin "35") (pinfunction "18_35") (pintype "passive"))
    )
    (net (code "73") (name "unconnected-(P1-19-Pad37)") (class "Default")
      (node (ref "P1") (pin "37") (pinfunction "19_37") (pintype "passive"))
    )
    (net (code "74") (name "unconnected-(P1-27-Pad4)") (class "Default")
      (node (ref "P1") (pin "4") (pinfunction "27_4") (pintype "passive"))
    )
    (net (code "75") (name "unconnected-(P1-28-Pad6)") (class "Default")
      (node (ref "P1") (pin "6") (pinfunction "28_6") (pintype "passive"))
    )
    (net (code "76") (name "unconnected-(P1-29-Pad8)") (class "Default")
      (node (ref "P1") (pin "8") (pinfunction "29_8") (pintype "passive"))
    )
    (net (code "77") (name "unconnected-(P1-30-Pad10)") (class "Default")
      (node (ref "P1") (pin "10") (pinfunction "30_10") (pintype "passive"))
    )
    (net (code "78") (name "unconnected-(P1-32-Pad14)") (class "Default")
      (node (ref "P1") (pin "14") (pinfunction "32_14") (pintype "passive"))
    )
    (net (code "79") (name "unconnected-(P1-33-Pad16)") (class "Default")
      (node (ref "P1") (pin "16") (pinfunction "33_16") (pintype "passive"))
    )
    (net (code "80") (name "unconnected-(P1-34-Pad18)") (class "Default")
      (node (ref "P1") (pin "18") (pinfunction "34_18") (pintype "passive"))
    )
    (net (code "81") (name "unconnected-(P1-36-Pad22)") (class "Default")
      (node (ref "P1") (pin "22") (pinfunction "36_22") (pintype "passive"))
    )
    (net (code "82") (name "unconnected-(P1-37-Pad24)") (class "Default")
      (node (ref "P1") (pin "24") (pinfunction "37_24") (pintype "passive"))
    )
    (net (code "83") (name "unconnected-(P1-38-Pad26)") (class "Default")
      (node (ref "P1") (pin "26") (pinfunction "38_26") (pintype "passive"))
    )
    (net (code "84") (name "unconnected-(P1-41-Pad32)") (class "Default")
      (node (ref "P1") (pin "32") (pinfunction "41_32") (pintype "passive"))
    )
    (net (code "85") (name "unconnected-(P1-42-Pad34)") (class "Default")
      (node (ref "P1") (pin "34") (pinfunction "42_34") (pintype "passive"))
    )
    (net (code "86") (name "unconnected-(P1-43-Pad36)") (class "Default")
      (node (ref "P1") (pin "36") (pinfunction "43_36") (pintype "passive"))
    )
    (net (code "87") (name "unconnected-(P1-44-Pad38)") (class "Default")
      (node (ref "P1") (pin "38") (pinfunction "44_38") (pintype "passive"))
    )
    (net (code "88") (name "unconnected-(P2-Pad5)") (class "Default")
      (node (ref "P2") (pin "5") (pinfunction "5_5") (pintype "passive"))
    )
    (net (code "89") (name "unconnected-(P2-Pad6)") (class "Default")
      (node (ref "P2") (pin "6") (pinfunction "6_6") (pintype "passive"))
    )
    (net (code "90") (name "unconnected-(P2-Pad7)") (class "Default")
      (node (ref "P2") (pin "7") (pinfunction "7_7") (pintype "passive"))
    )
    (net (code "91") (name "unconnected-(P2-Pad8)") (class "Default")
      (node (ref "P2") (pin "8") (pinfunction "8_8") (pintype "passive"))
    )
    (net (code "92") (name "unconnected-(P2-Pad9)") (class "Default")
      (node (ref "P2") (pin "9") (pinfunction "9_9") (pintype "passive"))
    )
    (net (code "93") (name "unconnected-(P2-Pad10)") (class "Default")
      (node (ref "P2") (pin "10") (pinfunction "10_10") (pintype "passive"))
    )
    (net (code "94") (name "unconnected-(P2-Pad11)") (class "Default")
      (node (ref "P2") (pin "11") (pinfunction "11_11") (pintype "passive"))
    )
    (net (code "95") (name "unconnected-(P2-Pad12)") (class "Default")
      (node (ref "P2") (pin "12") (pinfunction "12_12") (pintype "passive"))
    )
    (net (code "96") (name "unconnected-(P2-Pad13)") (class "Default")
      (node (ref "P2") (pin "13") (pinfunction "13_13") (pintype "passive"))
    )
    (net (code "97") (name "unconnected-(P2-Pad14)") (class "Default")
      (node (ref "P2") (pin "14") (pinfunction "14_14") (pintype "passive"))
    )
    (net (code "98") (name "unconnected-(P2-Pad15)") (class "Default")
      (node (ref "P2") (pin "15") (pinfunction "15_15") (pintype "passive"))
    )
    (net (code "99") (name "unconnected-(P2-Pad16)") (class "Default")
      (node (ref "P2") (pin "16") (pinfunction "16_16") (pintype "passive"))
    )
    (net (code "100") (name "unconnected-(P2-Pad17)") (class "Default")
      (node (ref "P2") (pin "17") (pinfunction "17_17") (pintype "passive"))
    )
    (net (code "101") (name "unconnected-(P2-Pad18)") (class "Default")
      (node (ref "P2") (pin "18") (pinfunction "18_18") (pintype "passive"))
    )
    (net (code "102") (name "unconnected-(P2-Pad21)") (class "Default")
      (node (ref "P2") (pin "21") (pinfunction "21_21") (pintype "passive"))
    )
    (net (code "103") (name "unconnected-(P2-Pad22)") (class "Default")
      (node (ref "P2") (pin "22") (pinfunction "22_22") (pintype "passive"))
    )
    (net (code "104") (name "unconnected-(P2-Pad23)") (class "Default")
      (node (ref "P2") (pin "23") (pinfunction "23_23") (pintype "passive"))
    )
    (net (code "105") (name "unconnected-(P2-Pad24)") (class "Default")
      (node (ref "P2") (pin "24") (pinfunction "24_24") (pintype "passive"))
    )
    (net (code "106") (name "unconnected-(P2-Pad25)") (class "Default")
      (node (ref "P2") (pin "25") (pinfunction "25_25") (pintype "passive"))
    )
    (net (code "107") (name "unconnected-(P2-Pad26)") (class "Default")
      (node (ref "P2") (pin "26") (pinfunction "26_26") (pintype "passive"))
    )
    (net (code "108") (name "unconnected-(P2-Pad31)") (class "Default")
      (node (ref "P2") (pin "31") (pinfunction "31_31") (pintype "passive"))
    )
    (net (code "109") (name "unconnected-(P2-Pad32)") (class "Default")
      (node (ref "P2") (pin "32") (pinfunction "32_32") (pintype "passive"))
    )
    (net (code "110") (name "unconnected-(U2-DLCKM-Pad54)") (class "Default")
      (node (ref "U2") (pin "54") (pinfunction "DLCKM_54") (pintype "output"))
    )
    (net (code "111") (name "unconnected-(U2-DLOMA-Pad17)") (class "Default")
      (node (ref "U2") (pin "17") (pinfunction "DLOMA_17") (pintype "output"))
    )
    (net (code "112") (name "unconnected-(U2-DLOMH-Pad77)") (class "Default")
      (node (ref "U2") (pin "77") (pinfunction "DLOMH_77") (pintype "output"))
    )
    (net (code "113") (name "unconnected-(U2-DLOPA-Pad18)") (class "Default")
      (node (ref "U2") (pin "18") (pinfunction "DLOPA_18") (pintype "output"))
    )
    (net (code "114") (name "unconnected-(U2-DLOPH-Pad78)") (class "Default")
      (node (ref "U2") (pin "78") (pinfunction "DLOPH_78") (pintype "output"))
    )
    (net (code "115") (name "unconnected-(U2-DMCKN-Pad111)") (class "Default")
      (node (ref "U2") (pin "111") (pinfunction "DMCKN_111") (pintype "output"))
    )
    (net (code "116") (name "unconnected-(U2-DMCKP-Pad103)") (class "Default")
      (node (ref "U2") (pin "103") (pinfunction "DMCKP_103") (pintype "output"))
    )
    (net (code "117") (name "unconnected-(U2-DMO1N-Pad110)") (class "Default")
      (node (ref "U2") (pin "110") (pinfunction "DMO1N_110") (pintype "output"))
    )
    (net (code "118") (name "unconnected-(U2-DMO1P-Pad102)") (class "Default")
      (node (ref "U2") (pin "102") (pinfunction "DMO1P_102") (pintype "output"))
    )
    (net (code "119") (name "unconnected-(U2-DMO2N-Pad112)") (class "Default")
      (node (ref "U2") (pin "112") (pinfunction "DMO2N_112") (pintype "output"))
    )
    (net (code "120") (name "unconnected-(U2-DMO2P-Pad104)") (class "Default")
      (node (ref "U2") (pin "104") (pinfunction "DMO2P_104") (pintype "output"))
    )
    (net (code "121") (name "unconnected-(U2-DMO3N-Pad109)") (class "Default")
      (node (ref "U2") (pin "109") (pinfunction "DMO3N_109") (pintype "output"))
    )
    (net (code "122") (name "unconnected-(U2-DMO3P-Pad101)") (class "Default")
      (node (ref "U2") (pin "101") (pinfunction "DMO3P_101") (pintype "output"))
    )
    (net (code "123") (name "unconnected-(U2-DMO4N-Pad113)") (class "Default")
      (node (ref "U2") (pin "113") (pinfunction "DMO4N_113") (pintype "output"))
    )
    (net (code "124") (name "unconnected-(U2-DMO4P-Pad105)") (class "Default")
      (node (ref "U2") (pin "105") (pinfunction "DMO4P_105") (pintype "output"))
    )
    (net (code "125") (name "unconnected-(U2-SDO-Pad52)") (class "Default")
      (node (ref "U2") (pin "52") (pinfunction "SDO_52") (pintype "output"))
    )
    (net (code "126") (name "unconnected-(U2-TAMON-Pad26)") (class "Default")
      (node (ref "U2") (pin "26") (pinfunction "TAMON_26") (pintype "output"))
    )
    (net (code "127") (name "unconnected-(U2-TENABLE-Pad49)") (class "Default")
      (node (ref "U2") (pin "49") (pinfunction "TENABLE_49") (pintype "input+no_connect"))
    )
    (net (code "128") (name "unconnected-(U2-TOUT-Pad65)") (class "Default")
      (node (ref "U2") (pin "65") (pinfunction "TOUT_65") (pintype "output"))
    )
    (net (code "129") (name "unconnected-(U2-XTRIG-Pad76)") (class "Default")
      (node (ref "U2") (pin "76") (pinfunction "XTRIG_76") (pintype "input+no_connect"))
    )
    (net (code "130") (name "unconnected-(U4-BYPASS-Pad4)") (class "Default")
      (node (ref "U4") (pin "4") (pinfunction "BYPASS_4") (pintype "bidirectional"))
    )
    (net (code "131") (name "unconnected-(U6-1A1-Pad47)") (class "Default")
      (node (ref "U6") (pin "47") (pinfunction "1A1_47") (pintype "bidirectional"))
    )
    (net (code "132") (name "unconnected-(U6-1A2-Pad46)") (class "Default")
      (node (ref "U6") (pin "46") (pinfunction "1A2_46") (pintype "bidirectional"))
    )
    (net (code "133") (name "unconnected-(U6-1B1-Pad2)") (class "Default")
      (node (ref "U6") (pin "2") (pinfunction "1B1_2") (pintype "bidirectional"))
    )
    (net (code "134") (name "unconnected-(U6-1B2-Pad3)") (class "Default")
      (node (ref "U6") (pin "3") (pinfunction "1B2_3") (pintype "bidirectional"))
    )
    (net (code "135") (name "unconnected-(U7-BYPASS-Pad4)") (class "Default")
      (node (ref "U7") (pin "4") (pinfunction "BYPASS_4") (pintype "bidirectional"))
    )
    (net (code "136") (name "unconnected-(U9-NC-Pad6)") (class "Default")
      (node (ref "U9") (pin "6") (pinfunction "NC_6") (pintype "passive"))
    )
    (net (code "137") (name "unconnected-(U9-NC-Pad9)") (class "Default")
      (node (ref "U9") (pin "9") (pinfunction "NC_9") (pintype "passive"))
    )
  )
)
